# SiNEDevBoard.net
KiCad netlist of a schematic drawn in EAGLE
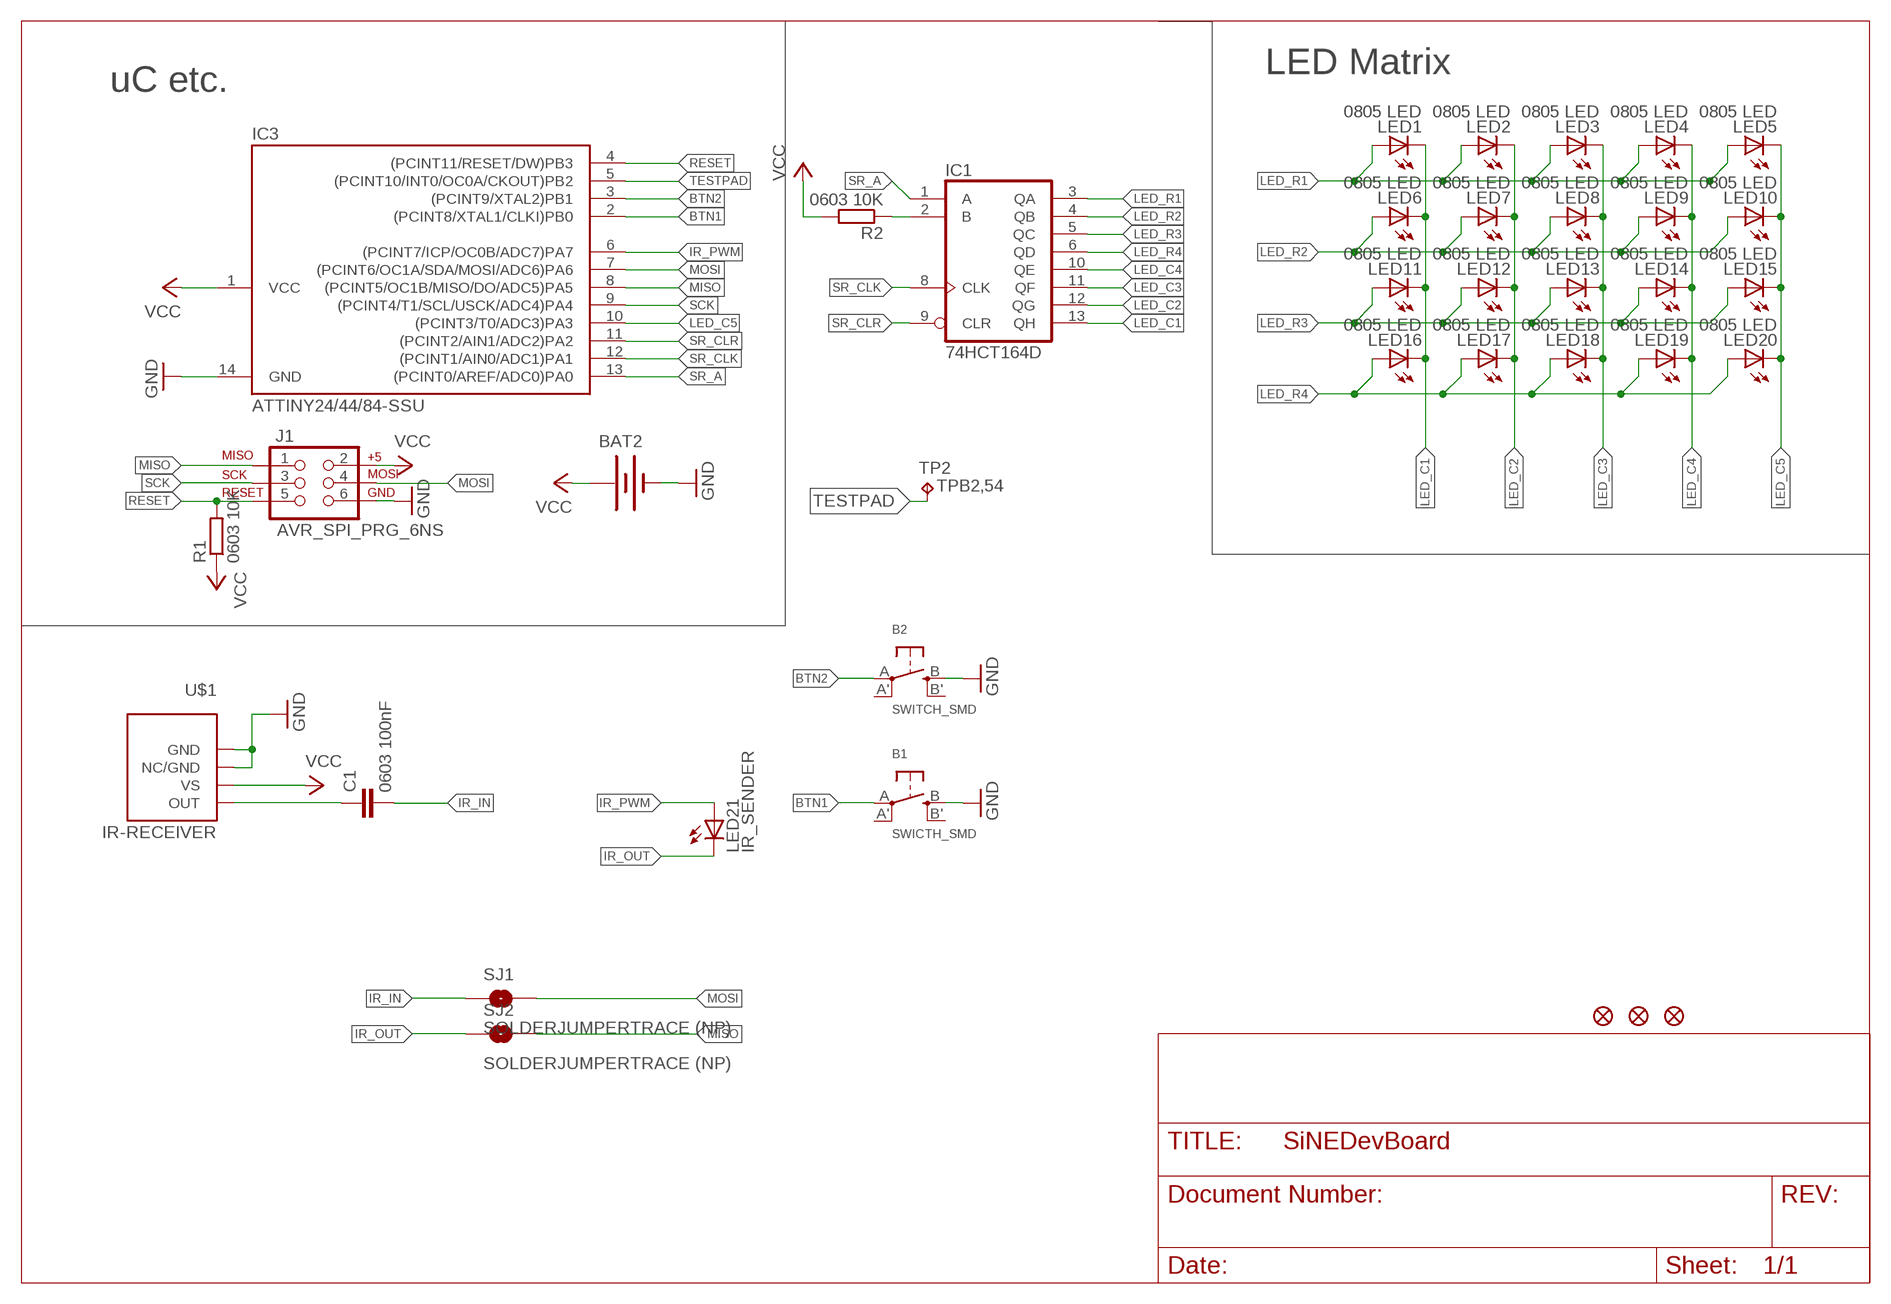
[diagram p0: schematic, sheet 1]

(export (version "E")
  (design (tool "Eeschema 10.0.6"))
  (components
    (comp (ref "B1")
      (value "SWICTH_SMD")
      (footprint "eagle-import:EVQ-Q2")
      (libsource (lib "eagle-import") (part "SWITCH_TACT_SMT"))
    )
    (comp (ref "B2")
      (value "SWITCH_SMD")
      (footprint "eagle-import:EVQ-Q2")
      (libsource (lib "eagle-import") (part "SWITCH_TACT_SMT"))
    )
    (comp (ref "BAT2")
      (value "BATTERY20SMD")
      (footprint "eagle-import:BATTCON_20MM")
      (libsource (lib "eagle-import") (part "BATTERY20SMD"))
    )
    (comp (ref "C1")
      (value "0603 100nF")
      (footprint "eagle-import:C0805")
      (libsource (lib "eagle-import") (part "C-EUC0805"))
    )
    (comp (ref "IC1")
      (value "74HCT164D")
      (footprint "eagle-import:SO14")
      (libsource (lib "eagle-import") (part "74164DHCT"))
    )
    (comp (ref "IC3")
      (value "ATTINY24/44/84-SSU")
      (footprint "eagle-import:SOIC14")
      (libsource (lib "eagle-import") (part "ATTINY24/44/84-SSU"))
    )
    (comp (ref "J1")
      (value "AVR_SPI_PRG_6NS")
      (footprint "eagle-import:2X3-NS")
      (libsource (lib "eagle-import") (part "AVR_SPI_PRG_6NS"))
    )
    (comp (ref "JP1")
      (value "FIDUCIAL1X2.5-STOP")
      (footprint "eagle-import:FIDUCIAL-1X2.5-STOP")
      (libsource (lib "eagle-import") (part "FIDUCIAL1X2.5-STOP"))
    )
    (comp (ref "JP2")
      (value "FIDUCIAL1X2.5-STOP")
      (footprint "eagle-import:FIDUCIAL-1X2.5-STOP")
      (libsource (lib "eagle-import") (part "FIDUCIAL1X2.5-STOP"))
    )
    (comp (ref "JP3")
      (value "FIDUCIAL1X2.5-STOP")
      (footprint "eagle-import:FIDUCIAL-1X2.5-STOP")
      (libsource (lib "eagle-import") (part "FIDUCIAL1X2.5-STOP"))
    )
    (comp (ref "LED1")
      (value "0805 LED")
      (footprint "eagle-import:CHIPLED_0805")
      (libsource (lib "eagle-import") (part "LEDCHIPLED_0805"))
    )
    (comp (ref "LED2")
      (value "0805 LED")
      (footprint "eagle-import:CHIPLED_0805")
      (libsource (lib "eagle-import") (part "LEDCHIPLED_0805"))
    )
    (comp (ref "LED3")
      (value "0805 LED")
      (footprint "eagle-import:CHIPLED_0805")
      (libsource (lib "eagle-import") (part "LEDCHIPLED_0805"))
    )
    (comp (ref "LED4")
      (value "0805 LED")
      (footprint "eagle-import:CHIPLED_0805")
      (libsource (lib "eagle-import") (part "LEDCHIPLED_0805"))
    )
    (comp (ref "LED5")
      (value "0805 LED")
      (footprint "eagle-import:CHIPLED_0805")
      (libsource (lib "eagle-import") (part "LEDCHIPLED_0805"))
    )
    (comp (ref "LED6")
      (value "0805 LED")
      (footprint "eagle-import:CHIPLED_0805")
      (libsource (lib "eagle-import") (part "LEDCHIPLED_0805"))
    )
    (comp (ref "LED7")
      (value "0805 LED")
      (footprint "eagle-import:CHIPLED_0805")
      (libsource (lib "eagle-import") (part "LEDCHIPLED_0805"))
    )
    (comp (ref "LED8")
      (value "0805 LED")
      (footprint "eagle-import:CHIPLED_0805")
      (libsource (lib "eagle-import") (part "LEDCHIPLED_0805"))
    )
    (comp (ref "LED9")
      (value "0805 LED")
      (footprint "eagle-import:CHIPLED_0805")
      (libsource (lib "eagle-import") (part "LEDCHIPLED_0805"))
    )
    (comp (ref "LED10")
      (value "0805 LED")
      (footprint "eagle-import:CHIPLED_0805")
      (libsource (lib "eagle-import") (part "LEDCHIPLED_0805"))
    )
    (comp (ref "LED11")
      (value "0805 LED")
      (footprint "eagle-import:CHIPLED_0805")
      (libsource (lib "eagle-import") (part "LEDCHIPLED_0805"))
    )
    (comp (ref "LED12")
      (value "0805 LED")
      (footprint "eagle-import:CHIPLED_0805")
      (libsource (lib "eagle-import") (part "LEDCHIPLED_0805"))
    )
    (comp (ref "LED13")
      (value "0805 LED")
      (footprint "eagle-import:CHIPLED_0805")
      (libsource (lib "eagle-import") (part "LEDCHIPLED_0805"))
    )
    (comp (ref "LED14")
      (value "0805 LED")
      (footprint "eagle-import:CHIPLED_0805")
      (libsource (lib "eagle-import") (part "LEDCHIPLED_0805"))
    )
    (comp (ref "LED15")
      (value "0805 LED")
      (footprint "eagle-import:CHIPLED_0805")
      (libsource (lib "eagle-import") (part "LEDCHIPLED_0805"))
    )
    (comp (ref "LED16")
      (value "0805 LED")
      (footprint "eagle-import:CHIPLED_0805")
      (libsource (lib "eagle-import") (part "LEDCHIPLED_0805"))
    )
    (comp (ref "LED17")
      (value "0805 LED")
      (footprint "eagle-import:CHIPLED_0805")
      (libsource (lib "eagle-import") (part "LEDCHIPLED_0805"))
    )
    (comp (ref "LED18")
      (value "0805 LED")
      (footprint "eagle-import:CHIPLED_0805")
      (libsource (lib "eagle-import") (part "LEDCHIPLED_0805"))
    )
    (comp (ref "LED19")
      (value "0805 LED")
      (footprint "eagle-import:CHIPLED_0805")
      (libsource (lib "eagle-import") (part "LEDCHIPLED_0805"))
    )
    (comp (ref "LED20")
      (value "0805 LED")
      (footprint "eagle-import:CHIPLED_0805")
      (libsource (lib "eagle-import") (part "LEDCHIPLED_0805"))
    )
    (comp (ref "LED21")
      (value "IR_SENDER")
      (footprint "eagle-import:CHIPLED_1206")
      (libsource (lib "eagle-import") (part "led_LEDCHIPLED_1206"))
    )
    (comp (ref "R1")
      (value "0603 10K")
      (footprint "eagle-import:R0805")
      (libsource (lib "eagle-import") (part "R-EU_R0805"))
    )
    (comp (ref "R2")
      (value "0603 10K")
      (footprint "eagle-import:R0805")
      (libsource (lib "eagle-import") (part "R-EU_R0805"))
    )
    (comp (ref "SJ1")
      (value "SOLDERJUMPERTRACE (NP)")
      (footprint "eagle-import:SJ_2S-TRACE")
      (libsource (lib "eagle-import") (part "SOLDERJUMPERTRACE"))
    )
    (comp (ref "SJ2")
      (value "SOLDERJUMPERTRACE (NP)")
      (footprint "eagle-import:SJ_2S-TRACE")
      (libsource (lib "eagle-import") (part "SOLDERJUMPERTRACE"))
    )
    (comp (ref "TP2")
      (value "TPB2,54")
      (footprint "eagle-import:B2,54")
      (libsource (lib "eagle-import") (part "TPB2,54"))
    )
    (comp (ref "U$1")
      (value "IR-RECEIVER")
      (footprint "eagle-import:TSOP35X")
      (libsource (lib "eagle-import") (part "IR-RECEIVER"))
    )
  )
  (nets
    (net (code "1") (name "BTN1") (class "Default")
      (node (ref "B1") (pin "A") (pinfunction "P_A") (pintype "passive"))
      (node (ref "IC3") (pin "2") (pinfunction "(PCINT8/XTAL1/CLKI)PB0_2") (pintype "bidirectional"))
    )
    (net (code "2") (name "BTN2") (class "Default")
      (node (ref "B2") (pin "A") (pinfunction "P_A") (pintype "passive"))
      (node (ref "IC3") (pin "3") (pinfunction "(PCINT9/XTAL2)PB1_3") (pintype "bidirectional"))
    )
    (net (code "3") (name "GND") (class "Default")
      (node (ref "B1") (pin "B") (pinfunction "S_B") (pintype "passive"))
      (node (ref "B2") (pin "B") (pinfunction "S_B") (pintype "passive"))
      (node (ref "BAT2") (pin "2") (pinfunction "-_2") (pintype "power_in"))
      (node (ref "IC3") (pin "14") (pinfunction "GND_14") (pintype "power_in"))
      (node (ref "J1") (pin "6") (pinfunction "6_6") (pintype "passive"))
      (node (ref "U$1") (pin "1") (pinfunction "GND_1") (pintype "bidirectional"))
      (node (ref "U$1") (pin "2") (pinfunction "NC/GND_2") (pintype "bidirectional"))
    )
    (net (code "4") (name "IR_IN") (class "Default")
      (node (ref "C1") (pin "2") (pinfunction "2_2") (pintype "passive"))
      (node (ref "SJ1") (pin "1") (pinfunction "1_1") (pintype "passive"))
    )
    (net (code "5") (name "IR_OUT") (class "Default")
      (node (ref "LED21") (pin "C") (pinfunction "C_C") (pintype "passive"))
      (node (ref "SJ2") (pin "1") (pinfunction "1_1") (pintype "passive"))
    )
    (net (code "6") (name "IR_PWM") (class "Default")
      (node (ref "IC3") (pin "6") (pinfunction "(PCINT7/ICP/OC0B/ADC7)PA7_6") (pintype "bidirectional"))
      (node (ref "LED21") (pin "A") (pinfunction "A_A") (pintype "passive"))
    )
    (net (code "7") (name "LED_C1") (class "Default")
      (node (ref "IC1") (pin "13") (pinfunction "QH_13") (pintype "output"))
      (node (ref "LED1") (pin "C") (pinfunction "C_C") (pintype "passive"))
      (node (ref "LED11") (pin "C") (pinfunction "C_C") (pintype "passive"))
      (node (ref "LED16") (pin "C") (pinfunction "C_C") (pintype "passive"))
      (node (ref "LED6") (pin "C") (pinfunction "C_C") (pintype "passive"))
    )
    (net (code "8") (name "LED_C2") (class "Default")
      (node (ref "IC1") (pin "12") (pinfunction "QG_12") (pintype "output"))
      (node (ref "LED12") (pin "C") (pinfunction "C_C") (pintype "passive"))
      (node (ref "LED17") (pin "C") (pinfunction "C_C") (pintype "passive"))
      (node (ref "LED2") (pin "C") (pinfunction "C_C") (pintype "passive"))
      (node (ref "LED7") (pin "C") (pinfunction "C_C") (pintype "passive"))
    )
    (net (code "9") (name "LED_C3") (class "Default")
      (node (ref "IC1") (pin "11") (pinfunction "QF_11") (pintype "output"))
      (node (ref "LED13") (pin "C") (pinfunction "C_C") (pintype "passive"))
      (node (ref "LED18") (pin "C") (pinfunction "C_C") (pintype "passive"))
      (node (ref "LED3") (pin "C") (pinfunction "C_C") (pintype "passive"))
      (node (ref "LED8") (pin "C") (pinfunction "C_C") (pintype "passive"))
    )
    (net (code "10") (name "LED_C4") (class "Default")
      (node (ref "IC1") (pin "10") (pinfunction "QE_10") (pintype "output"))
      (node (ref "LED14") (pin "C") (pinfunction "C_C") (pintype "passive"))
      (node (ref "LED19") (pin "C") (pinfunction "C_C") (pintype "passive"))
      (node (ref "LED4") (pin "C") (pinfunction "C_C") (pintype "passive"))
      (node (ref "LED9") (pin "C") (pinfunction "C_C") (pintype "passive"))
    )
    (net (code "11") (name "LED_C5") (class "Default")
      (node (ref "IC3") (pin "10") (pinfunction "(PCINT3/T0/ADC3)PA3_10") (pintype "bidirectional"))
      (node (ref "LED10") (pin "C") (pinfunction "C_C") (pintype "passive"))
      (node (ref "LED15") (pin "C") (pinfunction "C_C") (pintype "passive"))
      (node (ref "LED20") (pin "C") (pinfunction "C_C") (pintype "passive"))
      (node (ref "LED5") (pin "C") (pinfunction "C_C") (pintype "passive"))
    )
    (net (code "12") (name "LED_R1") (class "Default")
      (node (ref "IC1") (pin "3") (pinfunction "QA_3") (pintype "output"))
      (node (ref "LED1") (pin "A") (pinfunction "A_A") (pintype "passive"))
      (node (ref "LED2") (pin "A") (pinfunction "A_A") (pintype "passive"))
      (node (ref "LED3") (pin "A") (pinfunction "A_A") (pintype "passive"))
      (node (ref "LED4") (pin "A") (pinfunction "A_A") (pintype "passive"))
      (node (ref "LED5") (pin "A") (pinfunction "A_A") (pintype "passive"))
    )
    (net (code "13") (name "LED_R2") (class "Default")
      (node (ref "IC1") (pin "4") (pinfunction "QB_4") (pintype "output"))
      (node (ref "LED10") (pin "A") (pinfunction "A_A") (pintype "passive"))
      (node (ref "LED6") (pin "A") (pinfunction "A_A") (pintype "passive"))
      (node (ref "LED7") (pin "A") (pinfunction "A_A") (pintype "passive"))
      (node (ref "LED8") (pin "A") (pinfunction "A_A") (pintype "passive"))
      (node (ref "LED9") (pin "A") (pinfunction "A_A") (pintype "passive"))
    )
    (net (code "14") (name "LED_R3") (class "Default")
      (node (ref "IC1") (pin "5") (pinfunction "QC_5") (pintype "output"))
      (node (ref "LED11") (pin "A") (pinfunction "A_A") (pintype "passive"))
      (node (ref "LED12") (pin "A") (pinfunction "A_A") (pintype "passive"))
      (node (ref "LED13") (pin "A") (pinfunction "A_A") (pintype "passive"))
      (node (ref "LED14") (pin "A") (pinfunction "A_A") (pintype "passive"))
      (node (ref "LED15") (pin "A") (pinfunction "A_A") (pintype "passive"))
    )
    (net (code "15") (name "LED_R4") (class "Default")
      (node (ref "IC1") (pin "6") (pinfunction "QD_6") (pintype "output"))
      (node (ref "LED16") (pin "A") (pinfunction "A_A") (pintype "passive"))
      (node (ref "LED17") (pin "A") (pinfunction "A_A") (pintype "passive"))
      (node (ref "LED18") (pin "A") (pinfunction "A_A") (pintype "passive"))
      (node (ref "LED19") (pin "A") (pinfunction "A_A") (pintype "passive"))
      (node (ref "LED20") (pin "A") (pinfunction "A_A") (pintype "passive"))
    )
    (net (code "16") (name "MISO") (class "Default")
      (node (ref "IC3") (pin "8") (pinfunction "(PCINT5/OC1B/MISO/DO/ADC5)PA5_8") (pintype "bidirectional"))
      (node (ref "J1") (pin "1") (pinfunction "1_1") (pintype "passive"))
      (node (ref "SJ2") (pin "2") (pinfunction "2_2") (pintype "passive"))
    )
    (net (code "17") (name "MOSI") (class "Default")
      (node (ref "IC3") (pin "7") (pinfunction "(PCINT6/OC1A/SDA/MOSI/ADC6)PA6_7") (pintype "bidirectional"))
      (node (ref "J1") (pin "4") (pinfunction "4_4") (pintype "passive"))
      (node (ref "SJ1") (pin "2") (pinfunction "2_2") (pintype "passive"))
    )
    (net (code "18") (name "Net-(IC1A-B)") (class "Default")
      (node (ref "IC1") (pin "2") (pinfunction "B_2") (pintype "input"))
      (node (ref "R2") (pin "1") (pinfunction "1_1") (pintype "passive"))
    )
    (net (code "19") (name "Net-(U$1-OUT)") (class "Default")
      (node (ref "C1") (pin "1") (pinfunction "1_1") (pintype "passive"))
      (node (ref "U$1") (pin "4") (pinfunction "OUT_4") (pintype "bidirectional"))
    )
    (net (code "20") (name "RESET") (class "Default")
      (node (ref "IC3") (pin "4") (pinfunction "(PCINT11/RESET/DW)PB3_4") (pintype "bidirectional"))
      (node (ref "J1") (pin "5") (pinfunction "5_5") (pintype "passive"))
      (node (ref "R1") (pin "2") (pinfunction "2_2") (pintype "passive"))
    )
    (net (code "21") (name "SCK") (class "Default")
      (node (ref "IC3") (pin "9") (pinfunction "(PCINT4/T1/SCL/USCK/ADC4)PA4_9") (pintype "bidirectional"))
      (node (ref "J1") (pin "3") (pinfunction "3_3") (pintype "passive"))
    )
    (net (code "22") (name "SR_A") (class "Default")
      (node (ref "IC1") (pin "1") (pinfunction "A_1") (pintype "input"))
      (node (ref "IC3") (pin "13") (pinfunction "(PCINT0/AREF/ADC0)PA0_13") (pintype "bidirectional"))
    )
    (net (code "23") (name "SR_CLK") (class "Default")
      (node (ref "IC1") (pin "8") (pinfunction "CLK_8") (pintype "input"))
      (node (ref "IC3") (pin "12") (pinfunction "(PCINT1/AIN0/ADC1)PA1_12") (pintype "bidirectional"))
    )
    (net (code "24") (name "SR_CLR") (class "Default")
      (node (ref "IC1") (pin "9") (pinfunction "CLR_9") (pintype "input"))
      (node (ref "IC3") (pin "11") (pinfunction "(PCINT2/AIN1/ADC2)PA2_11") (pintype "bidirectional"))
    )
    (net (code "25") (name "TESTPAD") (class "Default")
      (node (ref "IC3") (pin "5") (pinfunction "(PCINT10/INT0/OC0A/CKOUT)PB2_5") (pintype "bidirectional"))
      (node (ref "TP2") (pin "TP") (pinfunction "TP_TP") (pintype "input"))
    )
    (net (code "26") (name "VCC") (class "Default")
      (node (ref "BAT2") (pin "1") (pinfunction "+_1") (pintype "power_in"))
      (node (ref "IC3") (pin "1") (pinfunction "VCC_1") (pintype "power_in"))
      (node (ref "J1") (pin "2") (pinfunction "2_2") (pintype "passive"))
      (node (ref "R1") (pin "1") (pinfunction "1_1") (pintype "passive"))
      (node (ref "R2") (pin "2") (pinfunction "2_2") (pintype "passive"))
      (node (ref "U$1") (pin "3") (pinfunction "VS_3") (pintype "bidirectional"))
    )
    (net (code "27") (name "unconnected-(B1-P1-PadA')") (class "Default")
      (node (ref "B1") (pin "A'") (pinfunction "P1_A'") (pintype "passive"))
    )
    (net (code "28") (name "unconnected-(B1-S1-PadB')") (class "Default")
      (node (ref "B1") (pin "B'") (pinfunction "S1_B'") (pintype "passive"))
    )
    (net (code "29") (name "unconnected-(B2-P1-PadA')") (class "Default")
      (node (ref "B2") (pin "A'") (pinfunction "P1_A'") (pintype "passive"))
    )
    (net (code "30") (name "unconnected-(B2-S1-PadB')") (class "Default")
      (node (ref "B2") (pin "B'") (pinfunction "S1_B'") (pintype "passive"))
    )
  )
)
